# S1_Main.net
KiCad netlist of a schematic drawn in Altium Designer
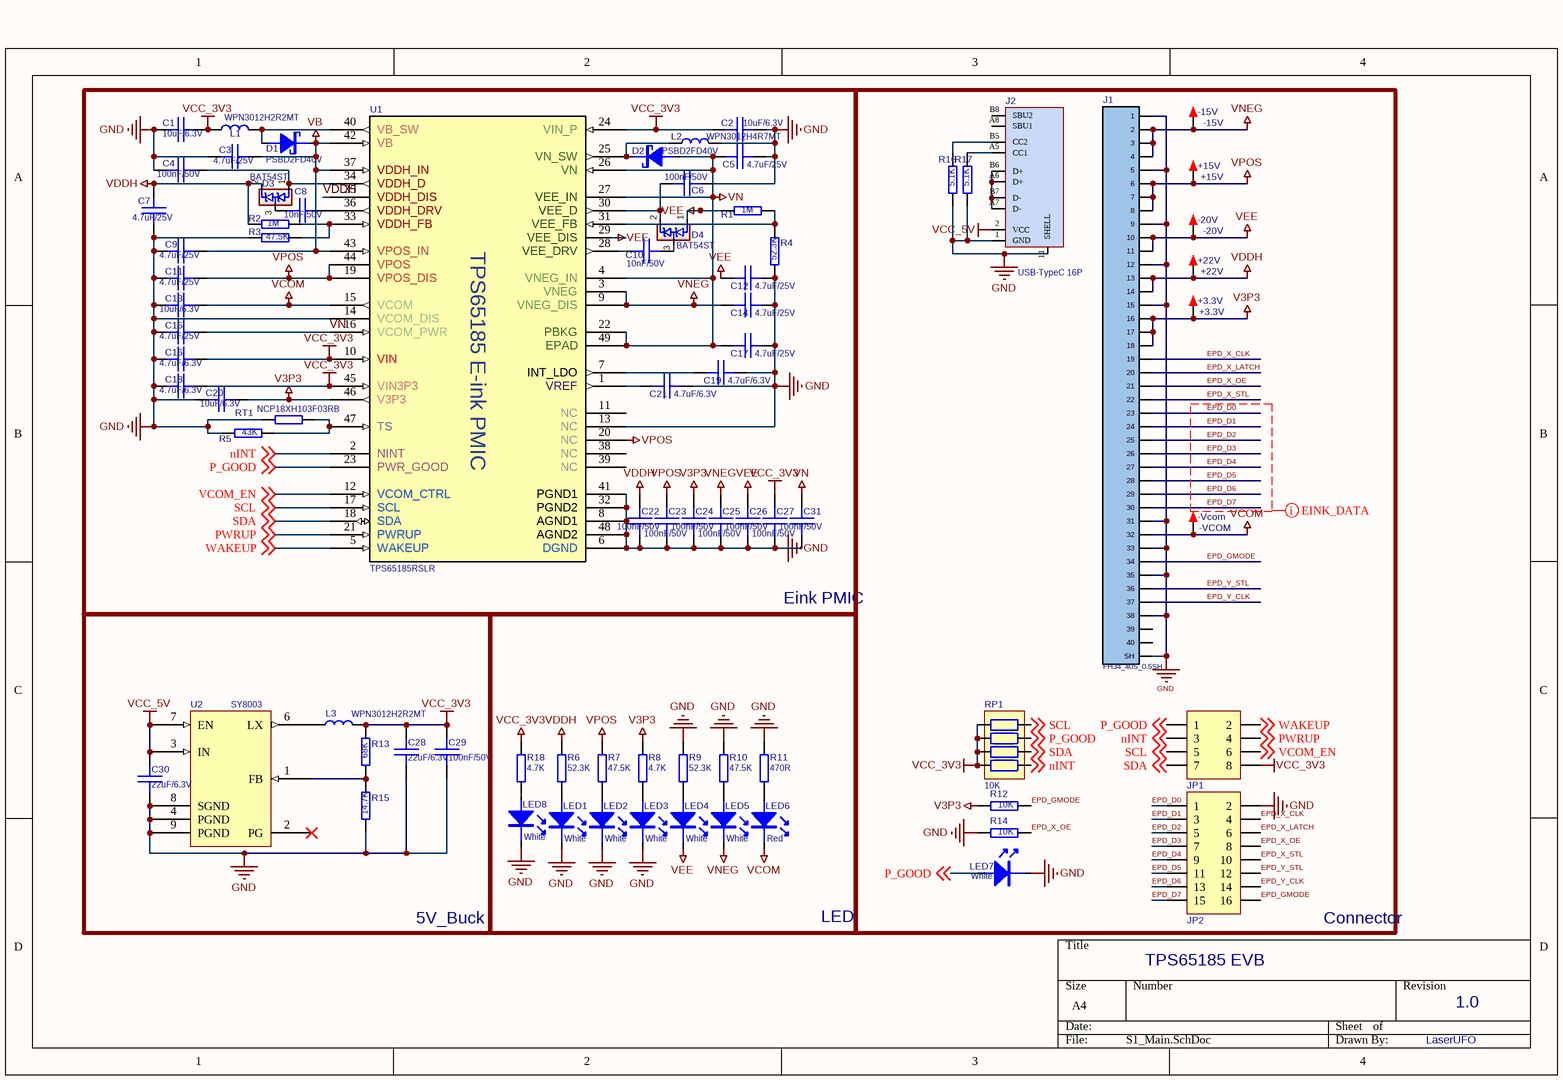
[diagram p0: S1_Main.SchDoc]

(export (version "E")
  (design (tool "Eeschema 10.0.6"))
  (components
    (comp (ref "+3.3V")
      (value "+3.3V")
      (footprint "TEST 1.4")
      (description "测试点")
      (fields (field (name "版权归属") "源创客"))
      (libsource (lib "15.1 - 未分类器件") (part "TEST"))
    )
    (comp (ref "+15V")
      (value "+15V")
      (footprint "TEST 1.4")
      (description "测试点")
      (fields (field (name "版权归属") "源创客"))
      (libsource (lib "15.1 - 未分类器件") (part "TEST"))
    )
    (comp (ref "+22V")
      (value "+22V")
      (footprint "TEST 1.4")
      (description "测试点")
      (fields (field (name "版权归属") "源创客"))
      (libsource (lib "15.1 - 未分类器件") (part "TEST"))
    )
    (comp (ref "-15V")
      (value "-15V")
      (footprint "TEST 1.4")
      (description "测试点")
      (fields (field (name "版权归属") "源创客"))
      (libsource (lib "15.1 - 未分类器件") (part "TEST"))
    )
    (comp (ref "-20V")
      (value "-20V")
      (footprint "TEST 1.4")
      (description "测试点")
      (fields (field (name "版权归属") "源创客"))
      (libsource (lib "15.1 - 未分类器件") (part "TEST"))
    )
    (comp (ref "-Vcom")
      (value "-VCOM")
      (footprint "TEST 1.4")
      (description "测试点")
      (fields (field (name "版权归属") "源创客"))
      (libsource (lib "15.1 - 未分类器件") (part "TEST"))
    )
    (comp (ref "C1")
      (value "10uF/6.3V")
      (footprint "SMT_C_0402")
      (description "SMT MLCC Capacitor")
      (libsource (lib "1_LCR_SMT") (part "SMT_C"))
    )
    (comp (ref "C2")
      (value "10uF/6.3V")
      (footprint "SMT_C_0402")
      (description "SMT MLCC Capacitor")
      (libsource (lib "1_LCR_SMT") (part "SMT_C"))
    )
    (comp (ref "C3")
      (value "4.7uF/25V")
      (footprint "SMT_C_0603")
      (description "SMT MLCC Capacitor")
      (libsource (lib "1_LCR_SMT") (part "SMT_C"))
    )
    (comp (ref "C4")
      (value "100nF/50V")
      (footprint "SMT_C_0402")
      (description "SMT MLCC Capacitor")
      (libsource (lib "1_LCR_SMT") (part "SMT_C"))
    )
    (comp (ref "C5")
      (value "4.7uF/25V")
      (footprint "SMT_C_0603")
      (description "SMT MLCC Capacitor")
      (libsource (lib "1_LCR_SMT") (part "SMT_C"))
    )
    (comp (ref "C6")
      (value "100nF/50V")
      (footprint "SMT_C_0402")
      (description "SMT MLCC Capacitor")
      (libsource (lib "1_LCR_SMT") (part "SMT_C"))
    )
    (comp (ref "C7")
      (value "4.7uF/25V")
      (footprint "SMT_C_0603")
      (description "SMT MLCC Capacitor")
      (libsource (lib "1_LCR_SMT") (part "SMT_C"))
    )
    (comp (ref "C8")
      (value "10nF/50V")
      (footprint "SMT_C_0402")
      (description "SMT MLCC Capacitor")
      (libsource (lib "1_LCR_SMT") (part "SMT_C"))
    )
    (comp (ref "C9")
      (value "4.7uF/25V")
      (footprint "SMT_C_0603")
      (description "SMT MLCC Capacitor")
      (libsource (lib "1_LCR_SMT") (part "SMT_C"))
    )
    (comp (ref "C10")
      (value "10nF/50V")
      (footprint "SMT_C_0402")
      (description "SMT MLCC Capacitor")
      (libsource (lib "1_LCR_SMT") (part "SMT_C"))
    )
    (comp (ref "C11")
      (value "4.7uF/25V")
      (footprint "SMT_C_0603")
      (description "SMT MLCC Capacitor")
      (libsource (lib "1_LCR_SMT") (part "SMT_C"))
    )
    (comp (ref "C12")
      (value "4.7uF/25V")
      (footprint "SMT_C_0603")
      (description "SMT MLCC Capacitor")
      (libsource (lib "1_LCR_SMT") (part "SMT_C"))
    )
    (comp (ref "C13")
      (value "10uF/6.3V")
      (footprint "SMT_C_0402")
      (description "SMT MLCC Capacitor")
      (libsource (lib "1_LCR_SMT") (part "SMT_C"))
    )
    (comp (ref "C14")
      (value "4.7uF/25V")
      (footprint "SMT_C_0603")
      (description "SMT MLCC Capacitor")
      (libsource (lib "1_LCR_SMT") (part "SMT_C"))
    )
    (comp (ref "C15")
      (value "4.7uF/25V")
      (footprint "SMT_C_0603")
      (description "SMT MLCC Capacitor")
      (libsource (lib "1_LCR_SMT") (part "SMT_C"))
    )
    (comp (ref "C16")
      (value "4.7uF/6.3V")
      (footprint "SMT_C_0402")
      (description "SMT MLCC Capacitor")
      (libsource (lib "1_LCR_SMT") (part "SMT_C"))
    )
    (comp (ref "C17")
      (value "4.7uF/25V")
      (footprint "SMT_C_0603")
      (description "SMT MLCC Capacitor")
      (libsource (lib "1_LCR_SMT") (part "SMT_C"))
    )
    (comp (ref "C18")
      (value "4.7uF/6.3V")
      (footprint "SMT_C_0402")
      (description "SMT MLCC Capacitor")
      (libsource (lib "1_LCR_SMT") (part "SMT_C"))
    )
    (comp (ref "C19")
      (value "4.7uF/6.3V")
      (footprint "SMT_C_0402")
      (description "SMT MLCC Capacitor")
      (libsource (lib "1_LCR_SMT") (part "SMT_C"))
    )
    (comp (ref "C20")
      (value "10uF/6.3V")
      (footprint "SMT_C_0402")
      (description "SMT MLCC Capacitor")
      (libsource (lib "1_LCR_SMT") (part "SMT_C"))
    )
    (comp (ref "C21")
      (value "4.7uF/6.3V")
      (footprint "SMT_C_0402")
      (description "SMT MLCC Capacitor")
      (libsource (lib "1_LCR_SMT") (part "SMT_C"))
    )
    (comp (ref "C22")
      (value "100nF/50V")
      (footprint "SMT_C_0402")
      (description "SMT MLCC Capacitor")
      (libsource (lib "1_LCR_SMT") (part "SMT_C"))
    )
    (comp (ref "C23")
      (value "100nF/50V")
      (footprint "SMT_C_0402")
      (description "SMT MLCC Capacitor")
      (libsource (lib "1_LCR_SMT") (part "SMT_C"))
    )
    (comp (ref "C24")
      (value "100nF/50V")
      (footprint "SMT_C_0402")
      (description "SMT MLCC Capacitor")
      (libsource (lib "1_LCR_SMT") (part "SMT_C"))
    )
    (comp (ref "C25")
      (value "100nF/50V")
      (footprint "SMT_C_0402")
      (description "SMT MLCC Capacitor")
      (libsource (lib "1_LCR_SMT") (part "SMT_C"))
    )
    (comp (ref "C26")
      (value "100nF/50V")
      (footprint "SMT_C_0402")
      (description "SMT MLCC Capacitor")
      (libsource (lib "1_LCR_SMT") (part "SMT_C"))
    )
    (comp (ref "C27")
      (value "100nF/50V")
      (footprint "SMT_C_0402")
      (description "SMT MLCC Capacitor")
      (libsource (lib "1_LCR_SMT") (part "SMT_C"))
    )
    (comp (ref "C28")
      (value "22uF/6.3V")
      (footprint "SMT_C_0603")
      (description "Surface mount capacitor 0603")
      (libsource (lib "Vowstar_Basic_Device") (part "SMT_C_0603"))
    )
    (comp (ref "C29")
      (value "100nF/50V")
      (footprint "SMT_C_0402")
      (description "SMT MLCC Capacitor")
      (libsource (lib "1_LCR_SMT") (part "SMT_C"))
    )
    (comp (ref "C30")
      (value "22uF/6.3V")
      (footprint "SMT_C_0603")
      (description "Surface mount capacitor 0603")
      (libsource (lib "Vowstar_Basic_Device") (part "SMT_C_0603"))
    )
    (comp (ref "C31")
      (value "100nF/50V")
      (footprint "SMT_C_0402")
      (description "SMT MLCC Capacitor")
      (libsource (lib "1_LCR_SMT") (part "SMT_C"))
    )
    (comp (ref "D1")
      (value "PSBD2FD40V")
      (footprint "SMT_DIODE_DFN1006-2L(0402)")
      (description "SMT Schottky diode")
      (libsource (lib "2_Diode_SMT") (part "SMT_DIODE_SCHOTTKY"))
    )
    (comp (ref "D2")
      (value "PSBD2FD40V")
      (footprint "SMT_DIODE_DFN1006-2L(0402)")
      (description "SMT Schottky diode")
      (libsource (lib "2_Diode_SMT") (part "SMT_DIODE_SCHOTTKY"))
    )
    (comp (ref "D3")
      (value "BAT54ST")
      (footprint "SOT523/SC-75")
      (description "Dual Schottky Diode_BAT54S")
      (libsource (lib "2_Diode_SMT") (part "SMT_DualDiode_BAT54S"))
    )
    (comp (ref "D4")
      (value "BAT54ST")
      (footprint "SOT523/SC-75")
      (description "Dual Schottky Diode_BAT54S")
      (libsource (lib "2_Diode_SMT") (part "SMT_DualDiode_BAT54S"))
    )
    (comp (ref "J1")
      (value "FH34_40S_0.5SH")
      (footprint "FPC_0.5MM_40P_DNUP_FH34SRJ-40S-0.5SH")
      (libsource (lib "LibMySelf_SCHLIB") (part "CON40_FPC_0.5"))
    )
    (comp (ref "J2")
      (value "USB-TypeC 16P")
      (footprint "USB-TYPE_C-16P")
      (description "USB TypeC female SMT with 4 fixed foot")
      (libsource (lib "1_Connector") (part "USB_Type_C_2.0_16P"))
    )
    (comp (ref "JP1")
      (value "Header 4X2")
      (footprint "HDR2.54-WI-2x4P")
      (description "4*2P接插件")
      (fields (field (name "版权归属") "源创客"))
      (libsource (lib "4.6   - 接插件-脚距2.54") (part "Header 4X2"))
    )
    (comp (ref "JP2")
      (value "Header 8X2")
      (footprint "HDR2.54-WI-2x8P")
      (description "8*2P接插件")
      (fields (field (name "版权归属") "源创客"))
      (libsource (lib "4.6   - 接插件-脚距2.54") (part "Header 8X2"))
    )
    (comp (ref "L1")
      (value "WPN3012H2R2MT")
      (footprint "SMT_L_3mm")
      (description "SMT Inductor")
      (libsource (lib "1_LCR_SMT") (part "SMT_L"))
    )
    (comp (ref "L2")
      (value "WPN3012H4R7MT")
      (footprint "SMT_L_3mm")
      (description "SMT Inductor")
      (libsource (lib "1_LCR_SMT") (part "SMT_L"))
    )
    (comp (ref "L3")
      (value "WPN3012H2R2MT")
      (footprint "SMT_L_3mm")
      (description "SMT Power Inductor, 3.3x3.3x1mm")
      (libsource (lib "Vowstar_Basic_Device") (part "SMT_L_3.0mm"))
    )
    (comp (ref "LED1")
      (value "White")
      (footprint "SMT_LED_0603_W")
      (description "SMT LED")
      (libsource (lib "2_Diode_SMT") (part "SMT_LED"))
    )
    (comp (ref "LED2")
      (value "White")
      (footprint "SMT_LED_0603_W")
      (description "SMT LED")
      (libsource (lib "2_Diode_SMT") (part "SMT_LED"))
    )
    (comp (ref "LED3")
      (value "White")
      (footprint "SMT_LED_0603_W")
      (description "SMT LED")
      (libsource (lib "2_Diode_SMT") (part "SMT_LED"))
    )
    (comp (ref "LED4")
      (value "White")
      (footprint "SMT_LED_0603_W")
      (description "SMT LED")
      (libsource (lib "2_Diode_SMT") (part "SMT_LED"))
    )
    (comp (ref "LED5")
      (value "White")
      (footprint "SMT_LED_0603_W")
      (description "SMT LED")
      (libsource (lib "2_Diode_SMT") (part "SMT_LED"))
    )
    (comp (ref "LED6")
      (value "Red")
      (footprint "SMT_LED_0603_W")
      (description "SMT LED")
      (libsource (lib "2_Diode_SMT") (part "SMT_LED"))
    )
    (comp (ref "LED7")
      (value "White")
      (footprint "SMT_LED_0603_W")
      (description "SMT LED")
      (libsource (lib "2_Diode_SMT") (part "SMT_LED"))
    )
    (comp (ref "LED8")
      (value "White")
      (footprint "SMT_LED_0603_W")
      (description "SMT LED")
      (libsource (lib "2_Diode_SMT") (part "SMT_LED"))
    )
    (comp (ref "R1")
      (value "1M")
      (footprint "SMT_R_0402")
      (description "SMT Resistor")
      (libsource (lib "1_LCR_SMT") (part "SMT_R"))
    )
    (comp (ref "R2")
      (value "1M")
      (footprint "SMT_R_0402")
      (description "SMT Resistor")
      (libsource (lib "1_LCR_SMT") (part "SMT_R"))
    )
    (comp (ref "R3")
      (value "47.5K")
      (footprint "SMT_R_0402")
      (description "SMT Resistor")
      (libsource (lib "1_LCR_SMT") (part "SMT_R"))
    )
    (comp (ref "R4")
      (value "52.3K")
      (footprint "SMT_R_0402")
      (description "SMT Resistor")
      (libsource (lib "1_LCR_SMT") (part "SMT_R"))
    )
    (comp (ref "R5")
      (value "43K")
      (footprint "SMT_R_0402")
      (description "SMT Resistor")
      (libsource (lib "1_LCR_SMT") (part "SMT_R"))
    )
    (comp (ref "R6")
      (value "52.3K")
      (footprint "SMT_R_0402")
      (description "Surface mount resistor 0402")
      (libsource (lib "1_LCR_SMT") (part "SMT_R_0402"))
    )
    (comp (ref "R7")
      (value "47.5K")
      (footprint "SMT_R_0402")
      (description "Surface mount resistor 0402")
      (libsource (lib "1_LCR_SMT") (part "SMT_R_0402"))
    )
    (comp (ref "R8")
      (value "4.7K")
      (footprint "SMT_R_0402")
      (description "Surface mount resistor 0402")
      (libsource (lib "1_LCR_SMT") (part "SMT_R_0402"))
    )
    (comp (ref "R9")
      (value "52.3K")
      (footprint "SMT_R_0402")
      (description "Surface mount resistor 0402")
      (libsource (lib "1_LCR_SMT") (part "SMT_R_0402"))
    )
    (comp (ref "R10")
      (value "47.5K")
      (footprint "SMT_R_0402")
      (description "Surface mount resistor 0402")
      (libsource (lib "1_LCR_SMT") (part "SMT_R_0402"))
    )
    (comp (ref "R11")
      (value "470R")
      (footprint "SMT_R_0402")
      (description "Surface mount resistor 0402")
      (libsource (lib "1_LCR_SMT") (part "SMT_R_0402"))
    )
    (comp (ref "R12")
      (value "10K")
      (footprint "SMT_R_0402")
      (description "SMT Resistor")
      (libsource (lib "1_LCR_SMT") (part "SMT_R"))
    )
    (comp (ref "R13")
      (value "68K")
      (footprint "SMT_R_0402")
      (description "Surface mount resistor 0402")
      (libsource (lib "1_LCR_SMT") (part "SMT_R_0402"))
    )
    (comp (ref "R14")
      (value "10K")
      (footprint "SMT_R_0402")
      (description "SMT Resistor")
      (libsource (lib "1_LCR_SMT") (part "SMT_R"))
    )
    (comp (ref "R15")
      (value "14.7K")
      (footprint "SMT_R_0402")
      (description "Surface mount resistor 0402")
      (libsource (lib "1_LCR_SMT") (part "SMT_R_0402"))
    )
    (comp (ref "R16")
      (value "5.1K")
      (footprint "SMT_R_0402")
      (description "SMT Resistor")
      (libsource (lib "1_LCR_SMT") (part "SMT_R"))
    )
    (comp (ref "R17")
      (value "5.1K")
      (footprint "SMT_R_0402")
      (description "SMT Resistor")
      (libsource (lib "1_LCR_SMT") (part "SMT_R"))
    )
    (comp (ref "R18")
      (value "4.7K")
      (footprint "SMT_R_0402")
      (description "Surface mount resistor 0402")
      (libsource (lib "1_LCR_SMT") (part "SMT_R_0402"))
    )
    (comp (ref "RP1")
      (value "10K")
      (footprint "RCA-8P4R-0402")
      (description "贴片网络排阻")
      (fields (field (name "版权归属") "源创客"))
      (libsource (lib "3.1   - 电阻-电容-电感") (part "R-8P4R"))
    )
    (comp (ref "RT1")
      (value "NCP18XH103F03RB")
      (footprint "SMT_R_0603")
      (description "SMT Resistor")
      (libsource (lib "1_LCR_SMT") (part "SMT_R"))
    )
    (comp (ref "U1")
      (value "TPS65185RSLR")
      (footprint "RSL48_4P4X4P4")
      (description "PMIC for E-Ink?Vizplex?Enabled Electronic Paper Display, with Active Discharge")
      (fields
        (field (name "MANUFACTURER_PART_NUMBER") "TPS651851RSLR")
        (field (name "GENERIC_PART_NUMBER") "TPS65185")
        (field (name "COPYRIGHT") "Copyright (C) 2018 Accelerated Designs. All rights reserved")
      )
      (libsource (lib "2_IC_Ti") (part "TPS65185RSLR"))
    )
    (comp (ref "U2")
      (value "SY8003")
      (footprint "DFN(PSON)8_50P200X65_HS-9N")
      (description "High Efficiency 5.5V, 3A continuous, 1MHz\r\nSynchronous Step Down Regulator")
      (libsource (lib "2_IC_Silergy") (part "SY8003"))
    )
  )
  (nets
    (net (code "1") (name "/EPD_D0") (class "Default")
      (node (ref "J1") (pin "23") (pinfunction "23_23") (pintype "passive"))
      (node (ref "JP2") (pin "1") (pinfunction "1_1") (pintype "passive"))
    )
    (net (code "2") (name "/EPD_D1") (class "Default")
      (node (ref "J1") (pin "24") (pinfunction "24_24") (pintype "passive"))
      (node (ref "JP2") (pin "3") (pinfunction "3_3") (pintype "passive"))
    )
    (net (code "3") (name "/EPD_D2") (class "Default")
      (node (ref "J1") (pin "25") (pinfunction "25_25") (pintype "passive"))
      (node (ref "JP2") (pin "5") (pinfunction "5_5") (pintype "passive"))
    )
    (net (code "4") (name "/EPD_D3") (class "Default")
      (node (ref "J1") (pin "26") (pinfunction "26_26") (pintype "passive"))
      (node (ref "JP2") (pin "7") (pinfunction "7_7") (pintype "passive"))
    )
    (net (code "5") (name "/EPD_D4") (class "Default")
      (node (ref "J1") (pin "27") (pinfunction "27_27") (pintype "passive"))
      (node (ref "JP2") (pin "9") (pinfunction "9_9") (pintype "passive"))
    )
    (net (code "6") (name "/EPD_D5") (class "Default")
      (node (ref "J1") (pin "28") (pinfunction "28_28") (pintype "passive"))
      (node (ref "JP2") (pin "11") (pinfunction "11_11") (pintype "passive"))
    )
    (net (code "7") (name "/EPD_D6") (class "Default")
      (node (ref "J1") (pin "29") (pinfunction "29_29") (pintype "passive"))
      (node (ref "JP2") (pin "13") (pinfunction "13_13") (pintype "passive"))
    )
    (net (code "8") (name "/EPD_D7") (class "Default")
      (node (ref "J1") (pin "30") (pinfunction "30_30") (pintype "passive"))
      (node (ref "JP2") (pin "15") (pinfunction "15_15") (pintype "passive"))
    )
    (net (code "9") (name "/EPD_GMODE") (class "Default")
      (node (ref "J1") (pin "34") (pinfunction "34_34") (pintype "passive"))
      (node (ref "JP2") (pin "16") (pinfunction "16_16") (pintype "passive"))
      (node (ref "R12") (pin "2") (pinfunction "2_2") (pintype "passive"))
    )
    (net (code "10") (name "/EPD_X_CLK") (class "Default")
      (node (ref "J1") (pin "19") (pinfunction "19_19") (pintype "passive"))
      (node (ref "JP2") (pin "4") (pinfunction "4_4") (pintype "passive"))
    )
    (net (code "11") (name "/EPD_X_LATCH") (class "Default")
      (node (ref "J1") (pin "20") (pinfunction "20_20") (pintype "passive"))
      (node (ref "JP2") (pin "6") (pinfunction "6_6") (pintype "passive"))
    )
    (net (code "12") (name "/EPD_X_OE") (class "Default")
      (node (ref "J1") (pin "21") (pinfunction "21_21") (pintype "passive"))
      (node (ref "JP2") (pin "8") (pinfunction "8_8") (pintype "passive"))
      (node (ref "R14") (pin "2") (pinfunction "2_2") (pintype "passive"))
    )
    (net (code "13") (name "/EPD_X_STL") (class "Default")
      (node (ref "J1") (pin "22") (pinfunction "22_22") (pintype "passive"))
      (node (ref "JP2") (pin "10") (pinfunction "10_10") (pintype "passive"))
    )
    (net (code "14") (name "/EPD_Y_CLK") (class "Default")
      (node (ref "J1") (pin "37") (pinfunction "37_37") (pintype "passive"))
      (node (ref "JP2") (pin "14") (pinfunction "14_14") (pintype "passive"))
    )
    (net (code "15") (name "/EPD_Y_STL") (class "Default")
      (node (ref "J1") (pin "36") (pinfunction "36_36") (pintype "passive"))
      (node (ref "JP2") (pin "12") (pinfunction "12_12") (pintype "passive"))
    )
    (net (code "16") (name "GND") (class "Default")
      (node (ref "C1") (pin "1") (pinfunction "1_1") (pintype "passive"))
      (node (ref "C11") (pin "2") (pinfunction "2_2") (pintype "passive"))
      (node (ref "C12") (pin "2") (pinfunction "2_2") (pintype "passive"))
      (node (ref "C13") (pin "2") (pinfunction "2_2") (pintype "passive"))
      (node (ref "C14") (pin "2") (pinfunction "2_2") (pintype "passive"))
      (node (ref "C15") (pin "2") (pinfunction "2_2") (pintype "passive"))
      (node (ref "C16") (pin "1") (pinfunction "1_1") (pintype "passive"))
      (node (ref "C17") (pin "2") (pinfunction "2_2") (pintype "passive"))
      (node (ref "C18") (pin "1") (pinfunction "1_1") (pintype "passive"))
      (node (ref "C19") (pin "2") (pinfunction "2_2") (pintype "passive"))
      (node (ref "C2") (pin "2") (pinfunction "2_2") (pintype "passive"))
      (node (ref "C20") (pin "2") (pinfunction "2_2") (pintype "passive"))
      (node (ref "C21") (pin "2") (pinfunction "2_2") (pintype "passive"))
      (node (ref "C22") (pin "1") (pinfunction "1_1") (pintype "passive"))
      (node (ref "C23") (pin "1") (pinfunction "1_1") (pintype "passive"))
      (node (ref "C24") (pin "1") (pinfunction "1_1") (pintype "passive"))
      (node (ref "C25") (pin "1") (pinfunction "1_1") (pintype "passive"))
      (node (ref "C26") (pin "1") (pinfunction "1_1") (pintype "passive"))
      (node (ref "C27") (pin "1") (pinfunction "1_1") (pintype "passive"))
      (node (ref "C28") (pin "2") (pinfunction "2_2") (pintype "passive"))
      (node (ref "C29") (pin "2") (pinfunction "2_2") (pintype "passive"))
      (node (ref "C3") (pin "2") (pinfunction "2_2") (pintype "passive"))
      (node (ref "C30") (pin "2") (pinfunction "2_2") (pintype "passive"))
      (node (ref "C31") (pin "1") (pinfunction "1_1") (pintype "passive"))
      (node (ref "C4") (pin "1") (pinfunction "1_1") (pintype "passive"))
      (node (ref "C5") (pin "2") (pinfunction "2_2") (pintype "passive"))
      (node (ref "C6") (pin "1") (pinfunction "1_1") (pintype "passive"))
      (node (ref "C7") (pin "2") (pinfunction "2_2") (pintype "passive"))
      (node (ref "C9") (pin "2") (pinfunction "2_2") (pintype "passive"))
      (node (ref "J1") (pin "0") (pinfunction "SH_0") (pintype "passive"))
      (node (ref "J1") (pin "1") (pinfunction "1_1") (pintype "passive"))
      (node (ref "J1") (pin "12") (pinfunction "12_12") (pintype "passive"))
      (node (ref "J1") (pin "15") (pinfunction "15_15") (pintype "passive"))
      (node (ref "J1") (pin "31") (pinfunction "31_31") (pintype "passive"))
      (node (ref "J1") (pin "33") (pinfunction "33_33") (pintype "passive"))
      (node (ref "J1") (pin "35") (pinfunction "35_35") (pintype "passive"))
      (node (ref "J1") (pin "38") (pinfunction "38_38") (pintype "passive"))
      (node (ref "J1") (pin "5") (pinfunction "5_5") (pintype "passive"))
      (node (ref "J1") (pin "9") (pinfunction "9_9") (pintype "passive"))
      (node (ref "J2") (pin "1") (pinfunction "GND_1") (pintype "passive"))
      (node (ref "J2") (pin "11") (pinfunction "SHELL_11") (pintype "passive"))
      (node (ref "JP2") (pin "2") (pinfunction "2_2") (pintype "passive"))
      (node (ref "L2") (pin "1") (pinfunction "1_1") (pintype "passive"))
      (node (ref "LED1") (pin "2") (pinfunction "K_2") (pintype "passive"))
      (node (ref "LED2") (pin "2") (pinfunction "K_2") (pintype "passive"))
      (node (ref "LED3") (pin "2") (pinfunction "K_2") (pintype "passive"))
      (node (ref "LED7") (pin "2") (pinfunction "K_2") (pintype "passive"))
      (node (ref "LED8") (pin "2") (pinfunction "K_2") (pintype "passive"))
      (node (ref "R10") (pin "1") (pinfunction "1_1") (pintype "passive"))
      (node (ref "R11") (pin "1") (pinfunction "1_1") (pintype "passive"))
      (node (ref "R14") (pin "1") (pinfunction "1_1") (pintype "passive"))
      (node (ref "R15") (pin "2") (pinfunction "2_2") (pintype "passive"))
      (node (ref "R16") (pin "1") (pinfunction "1_1") (pintype "passive"))
      (node (ref "R17") (pin "1") (pinfunction "1_1") (pintype "passive"))
      (node (ref "R3") (pin "2") (pinfunction "2_2") (pintype "passive"))
      (node (ref "R4") (pin "2") (pinfunction "2_2") (pintype "passive"))
      (node (ref "R5") (pin "2") (pinfunction "2_2") (pintype "passive"))
      (node (ref "R9") (pin "1") (pinfunction "1_1") (pintype "passive"))
      (node (ref "RT1") (pin "1") (pinfunction "1_1") (pintype "passive"))
      (node (ref "U1") (pin "13") (pinfunction "NC_13") (pintype "passive"))
      (node (ref "U1") (pin "14") (pinfunction "VCOM_DIS_14") (pintype "power_in"))
      (node (ref "U1") (pin "32") (pinfunction "PGND2_32") (pintype "power_in"))
      (node (ref "U1") (pin "41") (pinfunction "PGND1_41") (pintype "power_in"))
      (node (ref "U1") (pin "48") (pinfunction "AGND2_48") (pintype "power_in"))
      (node (ref "U1") (pin "6") (pinfunction "DGND_6") (pintype "power_in"))
      (node (ref "U1") (pin "8") (pinfunction "AGND1_8") (pintype "power_in"))
      (node (ref "U2") (pin "4") (pinfunction "PGND_4") (pintype "power_in"))
      (node (ref "U2") (pin "8") (pinfunction "SGND_8") (pintype "power_in"))
      (node (ref "U2") (pin "9") (pinfunction "PGND_9") (pintype "power_in"))
    )
    (net (code "17") (name "Net-(C8-Pad2)") (class "Default")
      (node (ref "C8") (pin "2") (pinfunction "2_2") (pintype "passive"))
      (node (ref "D3") (pin "3") (pinfunction "3_3") (pintype "passive"))
    )
    (net (code "18") (name "Net-(C10-Pad1)") (class "Default")
      (node (ref "C10") (pin "1") (pinfunction "1_1") (pintype "passive"))
      (node (ref "D4") (pin "3") (pinfunction "3_3") (pintype "passive"))
    )
    (net (code "19") (name "Net-(D1-A)") (class "Default")
      (node (ref "D1") (pin "1") (pinfunction "A_1") (pintype "passive"))
      (node (ref "L1") (pin "1") (pinfunction "1_1") (pintype "passive"))
      (node (ref "U1") (pin "40") (pinfunction "VB_SW_40") (pintype "output"))
    )
    (net (code "20") (name "Net-(D2-K)") (class "Default")
      (node (ref "D2") (pin "2") (pinfunction "K_2") (pintype "passive"))
      (node (ref "L2") (pin "2") (pinfunction "2_2") (pintype "passive"))
      (node (ref "U1") (pin "25") (pinfunction "VN_SW_25") (pintype "output"))
    )
    (net (code "21") (name "Net-(J2-CC1)") (class "Default")
      (node (ref "J2") (pin "A5") (pinfunction "CC1_A5") (pintype "passive"))
      (node (ref "R17") (pin "2") (pinfunction "2_2") (pintype "passive"))
    )
    (net (code "22") (name "Net-(J2-CC2)") (class "Default")
      (node (ref "J2") (pin "B5") (pinfunction "CC2_B5") (pintype "passive"))
      (node (ref "R16") (pin "2") (pinfunction "2_2") (pintype "passive"))
    )
    (net (code "23") (name "Net-(J2-D+-PadA6)") (class "Default")
      (node (ref "J2") (pin "A6") (pinfunction "D+_A6") (pintype "passive"))
      (node (ref "J2") (pin "A7") (pinfunction "D-_A7") (pintype "passive"))
      (node (ref "J2") (pin "B6") (pinfunction "D+_B6") (pintype "passive"))
      (node (ref "J2") (pin "B7") (pinfunction "D-_B7") (pintype "passive"))
    )
    (net (code "24") (name "Net-(LED1-A)") (class "Default")
      (node (ref "LED1") (pin "1") (pinfunction "A_1") (pintype "passive"))
      (node (ref "R6") (pin "2") (pinfunction "2_2") (pintype "passive"))
    )
    (net (code "25") (name "Net-(LED2-A)") (class "Default")
      (node (ref "LED2") (pin "1") (pinfunction "A_1") (pintype "passive"))
      (node (ref "R7") (pin "2") (pinfunction "2_2") (pintype "passive"))
    )
    (net (code "26") (name "Net-(LED3-A)") (class "Default")
      (node (ref "LED3") (pin "1") (pinfunction "A_1") (pintype "passive"))
      (node (ref "R8") (pin "2") (pinfunction "2_2") (pintype "passive"))
    )
    (net (code "27") (name "Net-(LED4-A)") (class "Default")
      (node (ref "LED4") (pin "1") (pinfunction "A_1") (pintype "passive"))
      (node (ref "R9") (pin "2") (pinfunction "2_2") (pintype "passive"))
    )
    (net (code "28") (name "Net-(LED5-A)") (class "Default")
      (node (ref "LED5") (pin "1") (pinfunction "A_1") (pintype "passive"))
      (node (ref "R10") (pin "2") (pinfunction "2_2") (pintype "passive"))
    )
    (net (code "29") (name "Net-(LED6-A)") (class "Default")
      (node (ref "LED6") (pin "1") (pinfunction "A_1") (pintype "passive"))
      (node (ref "R11") (pin "2") (pinfunction "2_2") (pintype "passive"))
    )
    (net (code "30") (name "Net-(LED8-A)") (class "Default")
      (node (ref "LED8") (pin "1") (pinfunction "A_1") (pintype "passive"))
      (node (ref "R18") (pin "2") (pinfunction "2_2") (pintype "passive"))
    )
    (net (code "31") (name "Net-(U1-INT_LDO)") (class "Default")
      (node (ref "C19") (pin "1") (pinfunction "1_1") (pintype "passive"))
      (node (ref "U1") (pin "7") (pinfunction "INT_LDO_7") (pintype "output"))
    )
    (net (code "32") (name "Net-(U1-TS)") (class "Default")
      (node (ref "R5") (pin "1") (pinfunction "1_1") (pintype "passive"))
      (node (ref "RT1") (pin "2") (pinfunction "2_2") (pintype "passive"))
      (node (ref "U1") (pin "47") (pinfunction "TS_47") (pintype "input"))
    )
    (net (code "33") (name "Net-(U1-VDDH_D)") (class "Default")
      (node (ref "C4") (pin "2") (pinfunction "2_2") (pintype "passive"))
      (node (ref "D3") (pin "1") (pinfunction "1_1") (pintype "passive"))
      (node (ref "U1") (pin "34") (pinfunction "VDDH_D_34") (pintype "output"))
    )
    (net (code "34") (name "Net-(U1-VDDH_DRV)") (class "Default")
      (node (ref "C8") (pin "1") (pinfunction "1_1") (pintype "passive"))
      (node (ref "U1") (pin "36") (pinfunction "VDDH_DRV_36") (pintype "output"))
    )
    (net (code "35") (name "Net-(U1-VDDH_FB)") (class "Default")
      (node (ref "R2") (pin "1") (pinfunction "1_1") (pintype "passive"))
      (node (ref "R3") (pin "1") (pinfunction "1_1") (pintype "passive"))
      (node (ref "U1") (pin "33") (pinfunction "VDDH_FB_33") (pintype "input"))
    )
    (net (code "36") (name "Net-(U1-VEE_D)") (class "Default")
      (node (ref "C6") (pin "2") (pinfunction "2_2") (pintype "passive"))
      (node (ref "D4") (pin "2") (pinfunction "2_2") (pintype "passive"))
      (node (ref "U1") (pin "30") (pinfunction "VEE_D_30") (pintype "output"))
    )
    (net (code "37") (name "Net-(U1-VEE_DRV)") (class "Default")
      (node (ref "C10") (pin "2") (pinfunction "2_2") (pintype "passive"))
      (node (ref "U1") (pin "28") (pinfunction "VEE_DRV_28") (pintype "output"))
    )
    (net (code "38") (name "Net-(U1-VEE_FB)") (class "Default")
      (node (ref "R1") (pin "2") (pinfunction "2_2") (pintype "passive"))
      (node (ref "R4") (pin "1") (pinfunction "1_1") (pintype "passive"))
      (node (ref "U1") (pin "31") (pinfunction "VEE_FB_31") (pintype "input"))
    )
    (net (code "39") (name "Net-(U1-VREF)") (class "Default")
      (node (ref "C21") (pin "1") (pinfunction "1_1") (pintype "passive"))
      (node (ref "U1") (pin "1") (pinfunction "VREF_1") (pintype "output"))
    )
    (net (code "40") (name "Net-(U2-FB)") (class "Default")
      (node (ref "R13") (pin "2") (pinfunction "2_2") (pintype "passive"))
      (node (ref "R15") (pin "1") (pinfunction "1_1") (pintype "passive"))
      (node (ref "U2") (pin "1") (pinfunction "FB_1") (pintype "input"))
    )
    (net (code "41") (name "Net-(U2-LX)") (class "Default")
      (node (ref "L3") (pin "2") (pinfunction "2_2") (pintype "passive"))
      (node (ref "U2") (pin "6") (pinfunction "LX_6") (pintype "output"))
    )
    (net (code "42") (name "PWRUP") (class "Default")
      (node (ref "JP1") (pin "4") (pinfunction "4_4") (pintype "passive"))
      (node (ref "U1") (pin "21") (pinfunction "PWRUP_21") (pintype "input"))
    )
    (net (code "43") (name "P_GOOD") (class "Default")
      (node (ref "JP1") (pin "1") (pinfunction "1_1") (pintype "passive"))
      (node (ref "LED7") (pin "1") (pinfunction "A_1") (pintype "passive"))
      (node (ref "RP1") (pin "3") (pinfunction "3_3") (pintype "passive"))
      (node (ref "U1") (pin "23") (pinfunction "PWR_GOOD_23") (pintype "open_collector"))
    )
    (net (code "44") (name "SCL") (class "Default")
      (node (ref "JP1") (pin "5") (pinfunction "5_5") (pintype "passive"))
      (node (ref "RP1") (pin "4") (pinfunction "4_4") (pintype "passive"))
      (node (ref "U1") (pin "17") (pinfunction "SCL_17") (pintype "input"))
    )
    (net (code "45") (name "SDA") (class "Default")
      (node (ref "JP1") (pin "7") (pinfunction "7_7") (pintype "passive"))
      (node (ref "RP1") (pin "2") (pinfunction "2_2") (pintype "passive"))
      (node (ref "U1") (pin "18") (pinfunction "SDA_18") (pintype "bidirectional"))
    )
    (net (code "46") (name "V3P3") (class "Default")
      (node (ref "+3.3V") (pin "1") (pinfunction "1_1") (pintype "passive"))
      (node (ref "C20") (pin "1") (pinfunction "1_1") (pintype "passive"))
      (node (ref "C24") (pin "2") (pinfunction "2_2") (pintype "passive"))
      (node (ref "J1") (pin "16") (pinfunction "16_16") (pintype "passive"))
      (node (ref "J1") (pin "17") (pinfunction "17_17") (pintype "passive"))
      (node (ref "J1") (pin "18") (pinfunction "18_18") (pintype "passive"))
      (node (ref "R12") (pin "1") (pinfunction "1_1") (pintype "passive"))
      (node (ref "R8") (pin "1") (pinfunction "1_1") (pintype "passive"))
      (node (ref "U1") (pin "46") (pinfunction "V3P3_46") (pintype "output"))
    )
    (net (code "47") (name "VB") (class "Default")
      (node (ref "C3") (pin "1") (pinfunction "1_1") (pintype "passive"))
      (node (ref "C9") (pin "1") (pinfunction "1_1") (pintype "passive"))
      (node (ref "D1") (pin "2") (pinfunction "K_2") (pintype "passive"))
      (node (ref "U1") (pin "37") (pinfunction "VDDH_IN_37") (pintype "input"))
      (node (ref "U1") (pin "42") (pinfunction "VB_42") (pintype "input"))
      (node (ref "U1") (pin "43") (pinfunction "VPOS_IN_43") (pintype "input"))
    )
    (net (code "48") (name "VCC_3V3") (class "Default")
      (node (ref "C1") (pin "2") (pinfunction "2_2") (pintype "passive"))
      (node (ref "C16") (pin "2") (pinfunction "2_2") (pintype "passive"))
      (node (ref "C18") (pin "2") (pinfunction "2_2") (pintype "passive"))
      (node (ref "C2") (pin "1") (pinfunction "1_1") (pintype "passive"))
      (node (ref "C27") (pin "2") (pinfunction "2_2") (pintype "passive"))
      (node (ref "C28") (pin "1") (pinfunction "1_1") (pintype "passive"))
      (node (ref "C29") (pin "1") (pinfunction "1_1") (pintype "passive"))
      (node (ref "JP1") (pin "8") (pinfunction "8_8") (pintype "passive"))
      (node (ref "L1") (pin "2") (pinfunction "2_2") (pintype "passive"))
      (node (ref "L3") (pin "1") (pinfunction "1_1") (pintype "passive"))
      (node (ref "R13") (pin "1") (pinfunction "1_1") (pintype "passive"))
      (node (ref "R18") (pin "1") (pinfunction "1_1") (pintype "passive"))
      (node (ref "RP1") (pin "5") (pinfunction "5_5") (pintype "passive"))
      (node (ref "RP1") (pin "6") (pinfunction "6_6") (pintype "passive"))
      (node (ref "RP1") (pin "7") (pinfunction "7_7") (pintype "passive"))
      (node (ref "RP1") (pin "8") (pinfunction "8_8") (pintype "passive"))
      (node (ref "U1") (pin "10") (pinfunction "VIN_10") (pintype "input"))
      (node (ref "U1") (pin "24") (pinfunction "VIN_P_24") (pintype "input"))
      (node (ref "U1") (pin "45") (pinfunction "VIN3P3_45") (pintype "input"))
    )
    (net (code "49") (name "VCC_5V") (class "Default")
      (node (ref "C30") (pin "1") (pinfunction "1_1") (pintype "passive"))
      (node (ref "J2") (pin "2") (pinfunction "VCC_2") (pintype "passive"))
      (node (ref "U2") (pin "3") (pinfunction "IN_3") (pintype "input"))
      (node (ref "U2") (pin "7") (pinfunction "EN_7") (pintype "input"))
    )
    (net (code "50") (name "VCOM") (class "Default")
      (node (ref "-Vcom") (pin "1") (pinfunction "1_1") (pintype "passive"))
      (node (ref "C13") (pin "1") (pinfunction "1_1") (pintype "passive"))
      (node (ref "J1") (pin "32") (pinfunction "32_32") (pintype "passive"))
      (node (ref "LED6") (pin "2") (pinfunction "K_2") (pintype "passive"))
      (node (ref "U1") (pin "15") (pinfunction "VCOM_15") (pintype "output"))
    )
    (net (code "51") (name "VCOM_EN") (class "Default")
      (node (ref "JP1") (pin "6") (pinfunction "6_6") (pintype "passive"))
      (node (ref "U1") (pin "12") (pinfunction "VCOM_CTRL_12") (pintype "input"))
    )
    (net (code "52") (name "VDDH") (class "Default")
      (node (ref "+22V") (pin "1") (pinfunction "1_1") (pintype "passive"))
      (node (ref "C22") (pin "2") (pinfunction "2_2") (pintype "passive"))
      (node (ref "C7") (pin "1") (pinfunction "1_1") (pintype "passive"))
      (node (ref "D3") (pin "2") (pinfunction "2_2") (pintype "passive"))
      (node (ref "J1") (pin "13") (pinfunction "13_13") (pintype "passive"))
      (node (ref "J1") (pin "14") (pinfunction "14_14") (pintype "passive"))
      (node (ref "R2") (pin "2") (pinfunction "2_2") (pintype "passive"))
      (node (ref "R6") (pin "1") (pinfunction "1_1") (pintype "passive"))
      (node (ref "U1") (pin "35") (pinfunction "VDDH_DIS_35") (pintype "power_in"))
    )
    (net (code "53") (name "VEE") (class "Default")
      (node (ref "-20V") (pin "1") (pinfunction "1_1") (pintype "passive"))
      (node (ref "C12") (pin "1") (pinfunction "1_1") (pintype "passive"))
      (node (ref "C26") (pin "2") (pinfunction "2_2") (pintype "passive"))
      (node (ref "D4") (pin "1") (pinfunction "1_1") (pintype "passive"))
      (node (ref "J1") (pin "10") (pinfunction "10_10") (pintype "passive"))
      (node (ref "J1") (pin "11") (pinfunction "11_11") (pintype "passive"))
      (node (ref "LED4") (pin "2") (pinfunction "K_2") (pintype "passive"))
      (node (ref "R1") (pin "1") (pinfunction "1_1") (pintype "passive"))
      (node (ref "U1") (pin "29") (pinfunction "VEE_DIS_29") (pintype "power_in"))
    )
    (net (code "54") (name "VN") (class "Default")
      (node (ref "C15") (pin "1") (pinfunction "1_1") (pintype "passive"))
      (node (ref "C17") (pin "1") (pinfunction "1_1") (pintype "passive"))
      (node (ref "C31") (pin "2") (pinfunction "2_2") (pintype "passive"))
      (node (ref "C5") (pin "1") (pinfunction "1_1") (pintype "passive"))
      (node (ref "D2") (pin "1") (pinfunction "A_1") (pintype "passive"))
      (node (ref "U1") (pin "16") (pinfunction "VCOM_PWR_16") (pintype "input"))
      (node (ref "U1") (pin "22") (pinfunction "PBKG_22") (pintype "passive"))
      (node (ref "U1") (pin "26") (pinfunction "VN_26") (pintype "input"))
      (node (ref "U1") (pin "27") (pinfunction "VEE_IN_27") (pintype "power_in"))
      (node (ref "U1") (pin "4") (pinfunction "VNEG_IN_4") (pintype "power_in"))
      (node (ref "U1") (pin "49") (pinfunction "EPAD_49") (pintype "passive"))
    )
    (net (code "55") (name "VNEG") (class "Default")
      (node (ref "-15V") (pin "1") (pinfunction "1_1") (pintype "passive"))
      (node (ref "C14") (pin "1") (pinfunction "1_1") (pintype "passive"))
      (node (ref "C25") (pin "2") (pinfunction "2_2") (pintype "passive"))
      (node (ref "J1") (pin "2") (pinfunction "2_2") (pintype "passive"))
      (node (ref "J1") (pin "3") (pinfunction "3_3") (pintype "passive"))
      (node (ref "J1") (pin "4") (pinfunction "4_4") (pintype "passive"))
      (node (ref "LED5") (pin "2") (pinfunction "K_2") (pintype "passive"))
      (node (ref "U1") (pin "3") (pinfunction "VNEG_3") (pintype "power_in"))
      (node (ref "U1") (pin "9") (pinfunction "VNEG_DIS_9") (pintype "power_in"))
    )
    (net (code "56") (name "VPOS") (class "Default")
      (node (ref "+15V") (pin "1") (pinfunction "1_1") (pintype "passive"))
      (node (ref "C11") (pin "1") (pinfunction "1_1") (pintype "passive"))
      (node (ref "C23") (pin "2") (pinfunction "2_2") (pintype "passive"))
      (node (ref "J1") (pin "6") (pinfunction "6_6") (pintype "passive"))
      (node (ref "J1") (pin "7") (pinfunction "7_7") (pintype "passive"))
      (node (ref "J1") (pin "8") (pinfunction "8_8") (pintype "passive"))
      (node (ref "R7") (pin "1") (pinfunction "1_1") (pintype "passive"))
      (node (ref "U1") (pin "19") (pinfunction "VPOS_DIS_19") (pintype "power_in"))
      (node (ref "U1") (pin "20") (pinfunction "NC_20") (pintype "passive"))
      (node (ref "U1") (pin "44") (pinfunction "VPOS_44") (pintype "power_in"))
    )
    (net (code "57") (name "WAKEUP") (class "Default")
      (node (ref "JP1") (pin "2") (pinfunction "2_2") (pintype "passive"))
      (node (ref "U1") (pin "5") (pinfunction "WAKEUP_5") (pintype "input"))
    )
    (net (code "58") (name "nINT") (class "Default")
      (node (ref "JP1") (pin "3") (pinfunction "3_3") (pintype "passive"))
      (node (ref "RP1") (pin "1") (pinfunction "1_1") (pintype "passive"))
      (node (ref "U1") (pin "2") (pinfunction "NINT_2") (pintype "open_collector"))
    )
    (net (code "59") (name "unconnected-(J1-Pad39)") (class "Default")
      (node (ref "J1") (pin "39") (pinfunction "39_39") (pintype "passive"))
    )
    (net (code "60") (name "unconnected-(J1-Pad40)") (class "Default")
      (node (ref "J1") (pin "40") (pinfunction "40_40") (pintype "passive"))
    )
    (net (code "61") (name "unconnected-(J2-SBU1-PadA8)") (class "Default")
      (node (ref "J2") (pin "A8") (pinfunction "SBU1_A8") (pintype "passive"))
    )
    (net (code "62") (name "unconnected-(J2-SBU2-PadB8)") (class "Default")
      (node (ref "J2") (pin "B8") (pinfunction "SBU2_B8") (pintype "passive"))
    )
    (net (code "63") (name "unconnected-(U1-NC-Pad11)") (class "Default")
      (node (ref "U1") (pin "11") (pinfunction "NC_11") (pintype "passive"))
    )
    (net (code "64") (name "unconnected-(U1-NC-Pad38)") (class "Default")
      (node (ref "U1") (pin "38") (pinfunction "NC_38") (pintype "passive"))
    )
    (net (code "65") (name "unconnected-(U1-NC-Pad39)") (class "Default")
      (node (ref "U1") (pin "39") (pinfunction "NC_39") (pintype "passive"))
    )
    (net (code "66") (name "unconnected-(U2-PG-Pad2)") (class "Default")
      (node (ref "U2") (pin "2") (pinfunction "PG_2") (pintype "open_collector+no_connect"))
    )
  )
)
